# USB_Micro_Power_to_lab_board_2015-11-16.net
KiCad netlist of a schematic drawn in EAGLE
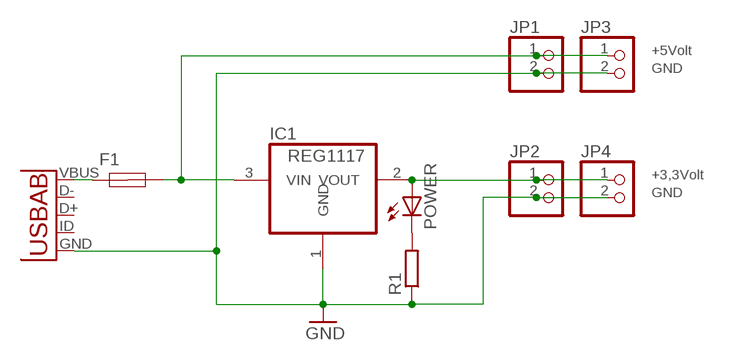
[diagram p0: schematic, sheet 1]

(export (version "E")
  (design (tool "Eeschema 10.0.6"))
  (components
    (comp (ref "F1")
      (value "LITTELFUSE_1812_500MA")
      (footprint "eagle-import:R1812")
      (fields (field (name "MPN") "1812L050PR"))
      (libsource (lib "eagle-import") (part "LITTELFUSE_1812_500MA"))
    )
    (comp (ref "IC1")
      (value "REG1117")
      (footprint "eagle-import:SOT223")
      (libsource (lib "eagle-import") (part "REG1117"))
    )
    (comp (ref "JP1")
      (value "PINHD-1X2")
      (footprint "eagle-import:1X02")
      (libsource (lib "eagle-import") (part "PINHD-1X2"))
    )
    (comp (ref "JP2")
      (value "PINHD-1X2")
      (footprint "eagle-import:1X02")
      (libsource (lib "eagle-import") (part "PINHD-1X2"))
    )
    (comp (ref "JP3")
      (value "PINHD-1X2")
      (footprint "eagle-import:1X02")
      (libsource (lib "eagle-import") (part "PINHD-1X2"))
    )
    (comp (ref "JP4")
      (value "PINHD-1X2")
      (footprint "eagle-import:1X02")
      (libsource (lib "eagle-import") (part "PINHD-1X2"))
    )
    (comp (ref "POWER")
      (value "LED3MM")
      (footprint "eagle-import:LED3MM")
      (libsource (lib "eagle-import") (part "LED3MM"))
    )
    (comp (ref "R1")
      (value "R-EU_0204/5")
      (footprint "eagle-import:0204_5")
      (libsource (lib "eagle-import") (part "R-EU_0204/5"))
    )
    (comp (ref "U1")
      (value "USB-ABUSB-AB-MICRO-SMD")
      (footprint "eagle-import:USB-AB-MICRO-SMD_VO2")
      (libsource (lib "eagle-import") (part "USB-ABUSB-AB-MICRO-SMD"))
    )
  )
  (nets
    (net (code "1") (name "GND") (class "Default")
      (node (ref "IC1") (pin "1") (pinfunction "GND_1") (pintype "power_in"))
      (node (ref "JP1") (pin "2") (pinfunction "2_2") (pintype "passive"))
      (node (ref "JP2") (pin "2") (pinfunction "2_2") (pintype "passive"))
      (node (ref "JP3") (pin "2") (pinfunction "2_2") (pintype "passive"))
      (node (ref "JP4") (pin "2") (pinfunction "2_2") (pintype "passive"))
      (node (ref "R1") (pin "1") (pinfunction "1_1") (pintype "passive"))
      (node (ref "U1") (pin "GND") (pinfunction "GND_GND") (pintype "bidirectional"))
    )
    (net (code "2") (name "Net-(F1-P$1)") (class "Default")
      (node (ref "F1") (pin "1") (pinfunction "P$1_1") (pintype "bidirectional"))
      (node (ref "U1") (pin "VBUS") (pinfunction "VBUS_VBUS") (pintype "bidirectional"))
    )
    (net (code "3") (name "Net-(F1-P$2)") (class "Default")
      (node (ref "F1") (pin "2") (pinfunction "P$2_2") (pintype "bidirectional"))
      (node (ref "IC1") (pin "3") (pinfunction "VIN_3") (pintype "input"))
      (node (ref "JP1") (pin "1") (pinfunction "1_1") (pintype "passive"))
      (node (ref "JP3") (pin "1") (pinfunction "1_1") (pintype "passive"))
    )
    (net (code "4") (name "Net-(IC1-VOUT)") (class "Default")
      (node (ref "IC1") (pin "2") (pinfunction "VOUT_2") (pintype "output"))
      (node (ref "JP2") (pin "1") (pinfunction "1_1") (pintype "passive"))
      (node (ref "JP4") (pin "1") (pinfunction "1_1") (pintype "passive"))
      (node (ref "POWER") (pin "A") (pinfunction "A_A") (pintype "passive"))
    )
    (net (code "5") (name "Net-(POWER-C)") (class "Default")
      (node (ref "POWER") (pin "K") (pinfunction "C_K") (pintype "passive"))
      (node (ref "R1") (pin "2") (pinfunction "2_2") (pintype "passive"))
    )
    (net (code "6") (name "unconnected-(U1-PadD+)") (class "Default")
      (node (ref "U1") (pin "D+") (pinfunction "D+_D+") (pintype "bidirectional"))
    )
    (net (code "7") (name "unconnected-(U1-PadD-)") (class "Default")
      (node (ref "U1") (pin "D-") (pinfunction "D-_D-") (pintype "bidirectional"))
    )
    (net (code "8") (name "unconnected-(U1-USBID-PadID)") (class "Default")
      (node (ref "U1") (pin "ID") (pinfunction "USBID_ID") (pintype "bidirectional"))
    )
  )
)
